# 14_ETHERNET.net
KiCad netlist of a schematic drawn in Altium Designer
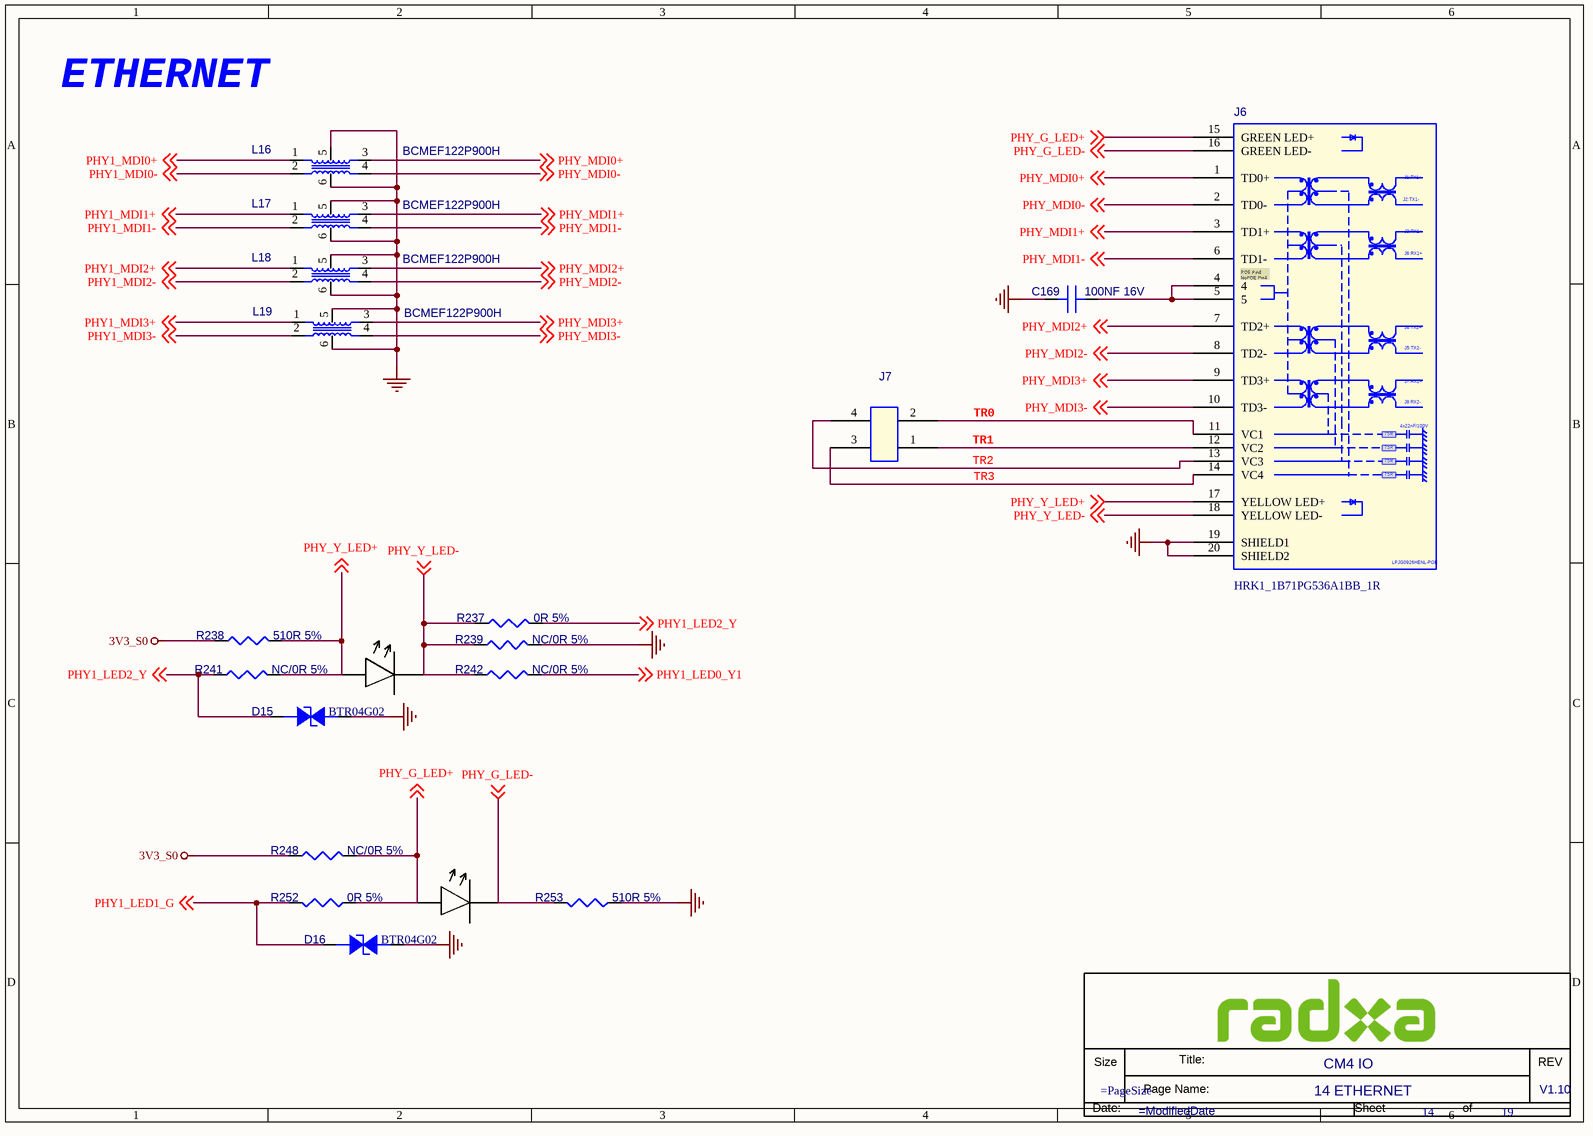
[diagram p0: 14 ETHERNET.SchDoc]

(export (version "E")
  (design (tool "Eeschema 10.0.6"))
  (components
    (comp (ref "C169")
      (value "100NF 16V")
      (footprint "C0201")
      (description "SMD  0201  100NF  16V  X5R  ±20%  ROHS")
      (fields (field (name "PART NUMBER") "A1C01.00099"))
      (libsource (lib "*") (part "C"))
    )
    (comp (ref "D15")
      (value "BTR04G02")
      (footprint "DFN1006-2L")
      (description "SMD  编带  0402  BTR04G02  B-tron  ROHS")
      (fields (field (name "PART NUMBER") "A1D02.00002"))
      (libsource (lib "*") (part "ESD"))
    )
    (comp (ref "D16")
      (value "BTR04G02")
      (footprint "DFN1006-2L")
      (description "SMD  编带  0402  BTR04G02  B-tron  ROHS")
      (fields (field (name "PART NUMBER") "A1D02.00002"))
      (libsource (lib "*") (part "ESD"))
    )
    (comp (ref "J6")
      (value "HRK1_1B71PG536A1BB_1R")
      (footprint "RJ45_LED_TH22_LIE")
      (description "DIP  母座  千兆网  带POE功能  18PIN  21.5*16*13.7mm  HRK1-1B71PG536A1BB-1R  镀镍  带指示灯  无弹片  左绿右黄  ROHS")
      (fields (field (name "PART NUMBER") "A1J03.00012"))
      (libsource (lib "*") (part "LPJG0926HENL"))
    )
    (comp (ref "J7")
      (value "~")
      (footprint "CONM_TH2X2_2D54_STA")
      (fields (field (name "PART NUMBER") "A1J01.00011"))
      (libsource (lib "*") (part "CON_2X2"))
    )
    (comp (ref "L16")
      (value "BCMEF122P900H")
      (footprint "CML_SM6_0D6_1D5")
      (description "SMD  BCMEF122P900H  90R  6PIN  带ESD  ±25%  B-tron  ROHS")
      (fields (field (name "PART NUMBER") "A1L03.00001"))
      (libsource (lib "*") (part "BCMEF122P900H"))
    )
    (comp (ref "L17")
      (value "BCMEF122P900H")
      (footprint "CML_SM6_0D6_1D5")
      (description "SMD  BCMEF122P900H  90R  6PIN  带ESD  ±25%  B-tron  ROHS")
      (fields (field (name "PART NUMBER") "A1L03.00001"))
      (libsource (lib "*") (part "BCMEF122P900H"))
    )
    (comp (ref "L18")
      (value "BCMEF122P900H")
      (footprint "CML_SM6_0D6_1D5")
      (description "SMD  BCMEF122P900H  90R  6PIN  带ESD  ±25%  B-tron  ROHS")
      (fields (field (name "PART NUMBER") "A1L03.00001"))
      (libsource (lib "*") (part "BCMEF122P900H"))
    )
    (comp (ref "L19")
      (value "BCMEF122P900H")
      (footprint "CML_SM6_0D6_1D5")
      (description "SMD  BCMEF122P900H  90R  6PIN  带ESD  ±25%  B-tron  ROHS")
      (fields (field (name "PART NUMBER") "A1L03.00001"))
      (libsource (lib "*") (part "BCMEF122P900H"))
    )
    (comp (ref "R237")
      (value "0R 5%")
      (footprint "R0402")
      (description "SMD  0201  0R  1/20W  ±5%  ROHS")
      (fields (field (name "PART NUMBER") "A1R01.00027"))
      (libsource (lib "*") (part "R"))
    )
    (comp (ref "R238")
      (value "510R 5%")
      (footprint "R0402")
      (description "SMD  0201  510R  1/20W  ±5%  ROHS")
      (fields (field (name "PART NUMBER") "A1R01.00019"))
      (libsource (lib "*") (part "R"))
    )
    (comp (ref "R239")
      (value "NC/0R 5%")
      (footprint "R0402")
      (description "SMD  0201  0R  1/20W  ±5%  ROHS")
      (fields (field (name "PART NUMBER") "A1R01.00027"))
      (libsource (lib "*") (part "R"))
    )
    (comp (ref "R241")
      (value "NC/0R 5%")
      (footprint "R0402")
      (description "SMD  0201  0R  1/20W  ±5%  ROHS")
      (fields (field (name "PART NUMBER") "A1R01.00027"))
      (libsource (lib "*") (part "R"))
    )
    (comp (ref "R242")
      (value "NC/0R 5%")
      (footprint "R0402")
      (description "SMD  0201  0R  1/20W  ±5%  ROHS")
      (fields (field (name "PART NUMBER") "A1R01.00027"))
      (libsource (lib "*") (part "R"))
    )
    (comp (ref "R248")
      (value "NC/0R 5%")
      (footprint "R0402")
      (description "SMD  0201  0R  1/20W  ±5%  ROHS")
      (fields (field (name "PART NUMBER") "A1R01.00027"))
      (libsource (lib "*") (part "R"))
    )
    (comp (ref "R252")
      (value "0R 5%")
      (footprint "R0402")
      (description "SMD  0201  0R  1/20W  ±5%  ROHS")
      (fields (field (name "PART NUMBER") "A1R01.00027"))
      (libsource (lib "*") (part "R"))
    )
    (comp (ref "R253")
      (value "510R 5%")
      (footprint "R0402")
      (description "SMD  0201  510R  1/20W  ±5%  ROHS")
      (fields (field (name "PART NUMBER") "A1R01.00019"))
      (libsource (lib "*") (part "R"))
    )
  )
  (nets
    (net (code "1") (name "/TR0") (class "Default")
      (node (ref "J6") (pin "11") (pinfunction "VC1_11") (pintype "passive"))
      (node (ref "J7") (pin "2") (pinfunction "2_2") (pintype "passive"))
    )
    (net (code "2") (name "/TR1") (class "Default")
      (node (ref "J6") (pin "12") (pinfunction "VC2_12") (pintype "passive"))
      (node (ref "J7") (pin "1") (pinfunction "1_1") (pintype "passive"))
    )
    (net (code "3") (name "/TR2") (class "Default")
      (node (ref "J6") (pin "13") (pinfunction "VC3_13") (pintype "passive"))
      (node (ref "J7") (pin "4") (pinfunction "4_4") (pintype "passive"))
    )
    (net (code "4") (name "/TR3") (class "Default")
      (node (ref "J6") (pin "14") (pinfunction "VC4_14") (pintype "passive"))
      (node (ref "J7") (pin "3") (pinfunction "3_3") (pintype "passive"))
    )
    (net (code "5") (name "3V3_S0") (class "Default")
      (node (ref "R238") (pin "1") (pinfunction "1_1") (pintype "passive"))
      (node (ref "R248") (pin "2") (pinfunction "2_2") (pintype "passive"))
    )
    (net (code "6") (name "GND") (class "Default")
      (node (ref "C169") (pin "1") (pinfunction "A_1") (pintype "passive"))
      (node (ref "D15") (pin "2") (pinfunction "CATHODE_2") (pintype "passive"))
      (node (ref "D16") (pin "2") (pinfunction "CATHODE_2") (pintype "passive"))
      (node (ref "J6") (pin "19") (pinfunction "SHIELD1_19") (pintype "passive"))
      (node (ref "J6") (pin "20") (pinfunction "SHIELD2_20") (pintype "passive"))
      (node (ref "L16") (pin "5") (pinfunction "5_5") (pintype "passive"))
      (node (ref "L16") (pin "6") (pinfunction "6_6") (pintype "passive"))
      (node (ref "L17") (pin "5") (pinfunction "5_5") (pintype "passive"))
      (node (ref "L17") (pin "6") (pinfunction "6_6") (pintype "passive"))
      (node (ref "L18") (pin "5") (pinfunction "5_5") (pintype "passive"))
      (node (ref "L18") (pin "6") (pinfunction "6_6") (pintype "passive"))
      (node (ref "L19") (pin "5") (pinfunction "5_5") (pintype "passive"))
      (node (ref "L19") (pin "6") (pinfunction "6_6") (pintype "passive"))
      (node (ref "R239") (pin "1") (pinfunction "1_1") (pintype "passive"))
      (node (ref "R253") (pin "2") (pinfunction "2_2") (pintype "passive"))
    )
    (net (code "7") (name "Net-(C169-B)") (class "Default")
      (node (ref "C169") (pin "2") (pinfunction "B_2") (pintype "passive"))
      (node (ref "J6") (pin "4") (pinfunction "4_4") (pintype "passive"))
      (node (ref "J6") (pin "5") (pinfunction "5_5") (pintype "passive"))
    )
    (net (code "8") (name "PHY1_LED0_Y1") (class "Default")
      (node (ref "R242") (pin "2") (pinfunction "2_2") (pintype "passive"))
    )
    (net (code "9") (name "PHY1_LED1_G") (class "Default")
      (node (ref "D16") (pin "1") (pinfunction "ANODE_1") (pintype "passive"))
      (node (ref "R252") (pin "1") (pinfunction "1_1") (pintype "passive"))
    )
    (net (code "10") (name "PHY1_LED2_Y") (class "Default")
      (node (ref "D15") (pin "1") (pinfunction "ANODE_1") (pintype "passive"))
      (node (ref "R237") (pin "2") (pinfunction "2_2") (pintype "passive"))
      (node (ref "R241") (pin "1") (pinfunction "1_1") (pintype "passive"))
    )
    (net (code "11") (name "PHY1_MDI0+") (class "Default")
      (node (ref "L16") (pin "1") (pinfunction "R1_1") (pintype "passive"))
    )
    (net (code "12") (name "PHY1_MDI0-") (class "Default")
      (node (ref "L16") (pin "2") (pinfunction "R2_2") (pintype "passive"))
    )
    (net (code "13") (name "PHY1_MDI1+") (class "Default")
      (node (ref "L17") (pin "1") (pinfunction "R1_1") (pintype "passive"))
    )
    (net (code "14") (name "PHY1_MDI1-") (class "Default")
      (node (ref "L17") (pin "2") (pinfunction "R2_2") (pintype "passive"))
    )
    (net (code "15") (name "PHY1_MDI2+") (class "Default")
      (node (ref "L18") (pin "1") (pinfunction "R1_1") (pintype "passive"))
    )
    (net (code "16") (name "PHY1_MDI2-") (class "Default")
      (node (ref "L18") (pin "2") (pinfunction "R2_2") (pintype "passive"))
    )
    (net (code "17") (name "PHY1_MDI3+") (class "Default")
      (node (ref "L19") (pin "1") (pinfunction "R1_1") (pintype "passive"))
    )
    (net (code "18") (name "PHY1_MDI3-") (class "Default")
      (node (ref "L19") (pin "2") (pinfunction "R2_2") (pintype "passive"))
    )
    (net (code "19") (name "PHY_G_LED+") (class "Default")
      (node (ref "J6") (pin "15") (pinfunction "GREEN_LED+_15") (pintype "passive"))
      (node (ref "R248") (pin "1") (pinfunction "1_1") (pintype "passive"))
      (node (ref "R252") (pin "2") (pinfunction "2_2") (pintype "passive"))
    )
    (net (code "20") (name "PHY_G_LED-") (class "Default")
      (node (ref "J6") (pin "16") (pinfunction "GREEN_LED-_16") (pintype "passive"))
      (node (ref "R253") (pin "1") (pinfunction "1_1") (pintype "passive"))
    )
    (net (code "21") (name "PHY_MDI0+") (class "Default")
      (node (ref "J6") (pin "1") (pinfunction "TD0+_1") (pintype "passive"))
      (node (ref "L16") (pin "3") (pinfunction "R4_3") (pintype "passive"))
    )
    (net (code "22") (name "PHY_MDI0-") (class "Default")
      (node (ref "J6") (pin "2") (pinfunction "TD0-_2") (pintype "passive"))
      (node (ref "L16") (pin "4") (pinfunction "R3_4") (pintype "passive"))
    )
    (net (code "23") (name "PHY_MDI1+") (class "Default")
      (node (ref "J6") (pin "3") (pinfunction "TD1+_3") (pintype "passive"))
      (node (ref "L17") (pin "3") (pinfunction "R4_3") (pintype "passive"))
    )
    (net (code "24") (name "PHY_MDI1-") (class "Default")
      (node (ref "J6") (pin "6") (pinfunction "TD1-_6") (pintype "passive"))
      (node (ref "L17") (pin "4") (pinfunction "R3_4") (pintype "passive"))
    )
    (net (code "25") (name "PHY_MDI2+") (class "Default")
      (node (ref "J6") (pin "7") (pinfunction "TD2+_7") (pintype "passive"))
      (node (ref "L18") (pin "3") (pinfunction "R4_3") (pintype "passive"))
    )
    (net (code "26") (name "PHY_MDI2-") (class "Default")
      (node (ref "J6") (pin "8") (pinfunction "TD2-_8") (pintype "passive"))
      (node (ref "L18") (pin "4") (pinfunction "R3_4") (pintype "passive"))
    )
    (net (code "27") (name "PHY_MDI3+") (class "Default")
      (node (ref "J6") (pin "9") (pinfunction "TD3+_9") (pintype "passive"))
      (node (ref "L19") (pin "3") (pinfunction "R4_3") (pintype "passive"))
    )
    (net (code "28") (name "PHY_MDI3-") (class "Default")
      (node (ref "J6") (pin "10") (pinfunction "TD3-_10") (pintype "passive"))
      (node (ref "L19") (pin "4") (pinfunction "R3_4") (pintype "passive"))
    )
    (net (code "29") (name "PHY_Y_LED+") (class "Default")
      (node (ref "J6") (pin "17") (pinfunction "YELLOW_LED+_17") (pintype "passive"))
      (node (ref "R238") (pin "2") (pinfunction "2_2") (pintype "passive"))
      (node (ref "R241") (pin "2") (pinfunction "2_2") (pintype "passive"))
    )
    (net (code "30") (name "PHY_Y_LED-") (class "Default")
      (node (ref "J6") (pin "18") (pinfunction "YELLOW_LED-_18") (pintype "passive"))
      (node (ref "R237") (pin "1") (pinfunction "1_1") (pintype "passive"))
      (node (ref "R239") (pin "2") (pinfunction "2_2") (pintype "passive"))
      (node (ref "R242") (pin "1") (pinfunction "1_1") (pintype "passive"))
    )
  )
)
